# tick-mini-mk-1_1.net
KiCad netlist of a schematic drawn in EAGLE
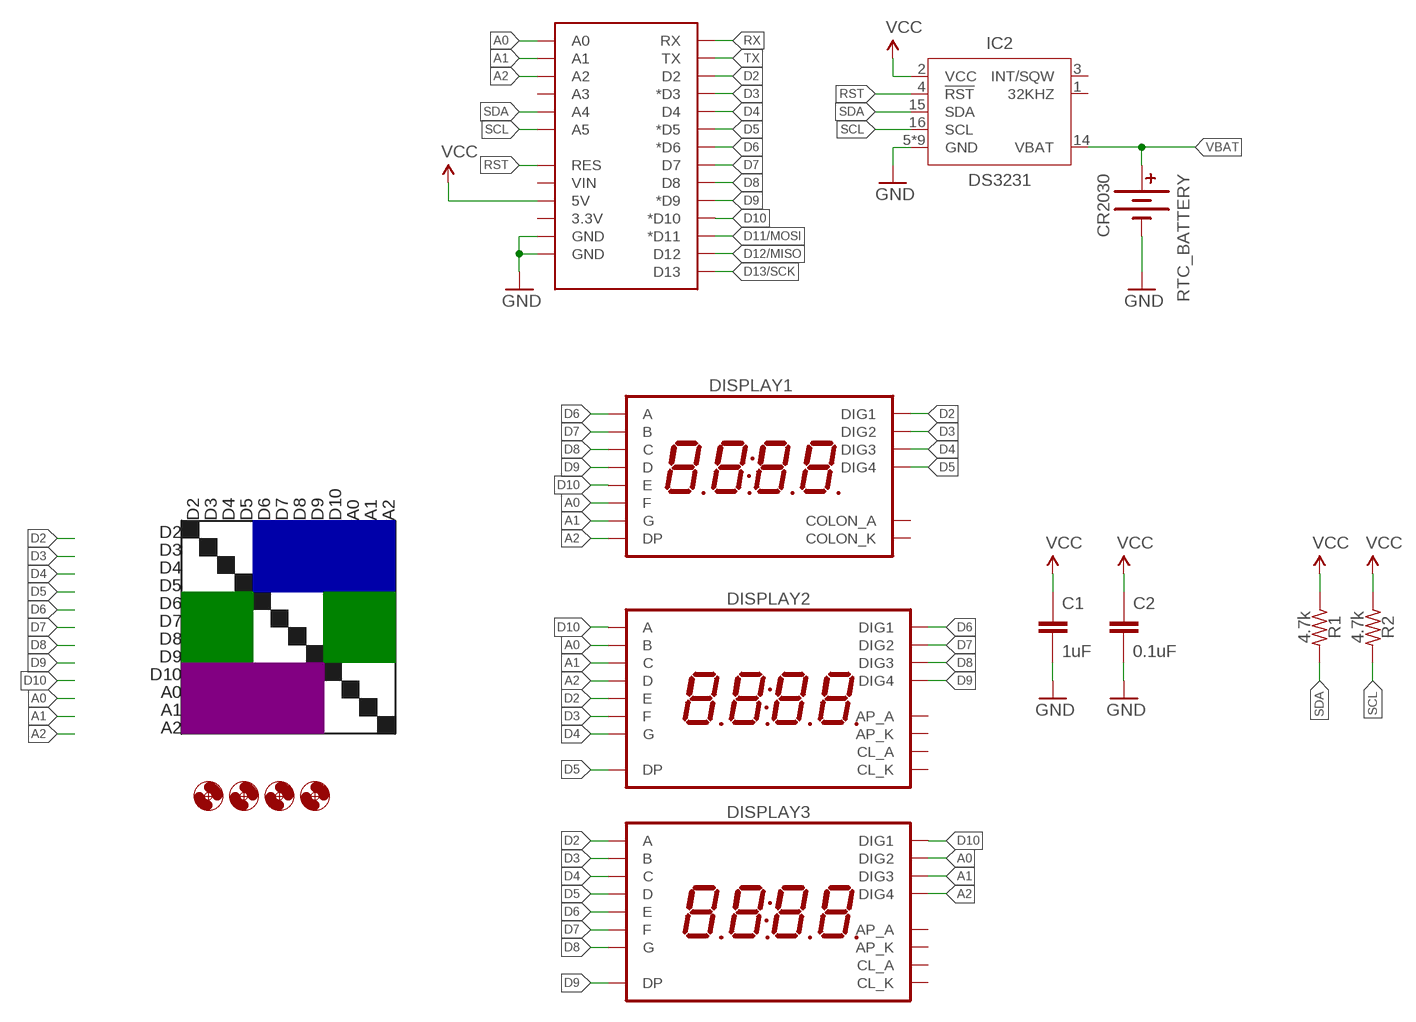
[diagram p0: schematic, sheet 1]

(export (version "E")
  (design (tool "Eeschema 10.0.6"))
  (components
    (comp (ref "C1")
      (value "1uF")
      (footprint "eagle-import:C025-024X044")
      (libsource (lib "eagle-import") (part "CAPACITOR-CERAMIC025-024X044"))
    )
    (comp (ref "C2")
      (value "0.1uF")
      (footprint "eagle-import:C025-024X044")
      (libsource (lib "eagle-import") (part "CAPACITOR-CERAMIC025-024X044"))
    )
    (comp (ref "DISPLAY1")
      (value "7SEG_4DIGIT_COLON14.2MM-CC-NS")
      (footprint "eagle-import:7SEG_4DIG_NS")
      (libsource (lib "eagle-import") (part "7SEG_4DIGIT_COLON14.2MM-CC-NS"))
    )
    (comp (ref "DISPLAY2")
      (value "7SEG_4DIGIT_COLON_APOS")
      (footprint "eagle-import:7SEG_4DIG_10MM")
      (libsource (lib "eagle-import") (part "7SEG_4DIGIT_COLON_APOS"))
    )
    (comp (ref "DISPLAY3")
      (value "7SEG_4DIGIT_COLON_APOS")
      (footprint "eagle-import:7SEG_4DIG_10MM")
      (libsource (lib "eagle-import") (part "7SEG_4DIGIT_COLON_APOS"))
    )
    (comp (ref "H1")
      (value "HOLE#2")
      (footprint "eagle-import:HOLE-#2")
      (libsource (lib "eagle-import") (part "HOLE#2"))
    )
    (comp (ref "H2")
      (value "HOLE#2")
      (footprint "eagle-import:HOLE-#2")
      (libsource (lib "eagle-import") (part "HOLE#2"))
    )
    (comp (ref "H3")
      (value "HOLE#2")
      (footprint "eagle-import:HOLE-#2")
      (libsource (lib "eagle-import") (part "HOLE#2"))
    )
    (comp (ref "H4")
      (value "HOLE#2")
      (footprint "eagle-import:HOLE-#2")
      (libsource (lib "eagle-import") (part "HOLE#2"))
    )
    (comp (ref "IC2")
      (value "DS3231")
      (footprint "eagle-import:SO16W")
      (libsource (lib "eagle-import") (part "DS3231"))
    )
    (comp (ref "R1")
      (value "4.7k")
      (footprint "eagle-import:RESISTOR-AXIAL-PTH-6.35MM")
      (libsource (lib "eagle-import") (part "RESISTORPTH-AXIAL-6.35MM"))
    )
    (comp (ref "R2")
      (value "4.7k")
      (footprint "eagle-import:RESISTOR-AXIAL-PTH-6.35MM")
      (libsource (lib "eagle-import") (part "RESISTORPTH-AXIAL-6.35MM"))
    )
    (comp (ref "RTC_BATTERY")
      (value "CR2030")
      (footprint "eagle-import:BATTCON_20MM_MINE")
      (libsource (lib "eagle-import") (part "BATTERY20MMSMD-MINE"))
    )
    (comp (ref "U$1")
      (value "ARDUINO_SHIELD_SMALLER")
      (footprint "eagle-import:ARDUINO_SHIELD_NOOUTLINE_INSIDE_SMALLER")
      (libsource (lib "eagle-import") (part "ARDUINO_SHIELD_SMALLER"))
    )
  )
  (nets
    (net (code "1") (name "A0") (class "Default")
      (node (ref "DISPLAY1") (pin "P$12") (pinfunction "F_P$12") (pintype "passive"))
      (node (ref "DISPLAY2") (pin "16") (pinfunction "B_16") (pintype "passive"))
      (node (ref "DISPLAY3") (pin "2") (pinfunction "DIG2_2") (pintype "passive"))
      (node (ref "U$1") (pin "A0") (pinfunction "A0_A0") (pintype "bidirectional"))
    )
    (net (code "2") (name "A1") (class "Default")
      (node (ref "DISPLAY1") (pin "P$5") (pinfunction "G_P$5") (pintype "passive"))
      (node (ref "DISPLAY2") (pin "13") (pinfunction "C_13") (pintype "passive"))
      (node (ref "DISPLAY3") (pin "6") (pinfunction "DIG3_6") (pintype "passive"))
      (node (ref "U$1") (pin "A1") (pinfunction "A1_A1") (pintype "bidirectional"))
    )
    (net (code "3") (name "A2") (class "Default")
      (node (ref "DISPLAY1") (pin "P$3") (pinfunction "DP_P$3") (pintype "passive"))
      (node (ref "DISPLAY2") (pin "3") (pinfunction "D_3") (pintype "passive"))
      (node (ref "DISPLAY3") (pin "8") (pinfunction "DIG4_8") (pintype "passive"))
      (node (ref "U$1") (pin "A2") (pinfunction "A2_A2") (pintype "bidirectional"))
    )
    (net (code "4") (name "D2") (class "Default")
      (node (ref "DISPLAY1") (pin "P$14") (pinfunction "DIG1_P$14") (pintype "passive"))
      (node (ref "DISPLAY2") (pin "5") (pinfunction "E_5") (pintype "passive"))
      (node (ref "DISPLAY3") (pin "14") (pinfunction "A_14") (pintype "passive"))
      (node (ref "U$1") (pin "D2") (pinfunction "D2_D2") (pintype "bidirectional"))
    )
    (net (code "5") (name "D3") (class "Default")
      (node (ref "DISPLAY1") (pin "P$11") (pinfunction "DIG2_P$11") (pintype "passive"))
      (node (ref "DISPLAY2") (pin "11") (pinfunction "F_11") (pintype "passive"))
      (node (ref "DISPLAY3") (pin "16") (pinfunction "B_16") (pintype "passive"))
      (node (ref "U$1") (pin "D3") (pinfunction "*D3_D3") (pintype "bidirectional"))
    )
    (net (code "6") (name "D4") (class "Default")
      (node (ref "DISPLAY1") (pin "P$10") (pinfunction "DIG3_P$10") (pintype "passive"))
      (node (ref "DISPLAY2") (pin "15") (pinfunction "G_15") (pintype "passive"))
      (node (ref "DISPLAY3") (pin "13") (pinfunction "C_13") (pintype "passive"))
      (node (ref "U$1") (pin "D4") (pinfunction "D4_D4") (pintype "bidirectional"))
    )
    (net (code "7") (name "D5") (class "Default")
      (node (ref "DISPLAY1") (pin "P$6") (pinfunction "DIG4_P$6") (pintype "passive"))
      (node (ref "DISPLAY2") (pin "7") (pinfunction "DP_7") (pintype "passive"))
      (node (ref "DISPLAY3") (pin "3") (pinfunction "D_3") (pintype "passive"))
      (node (ref "U$1") (pin "D5") (pinfunction "*D5_D5") (pintype "bidirectional"))
    )
    (net (code "8") (name "D6") (class "Default")
      (node (ref "DISPLAY1") (pin "P$13") (pinfunction "A_P$13") (pintype "passive"))
      (node (ref "DISPLAY2") (pin "1") (pinfunction "DIG1_1") (pintype "passive"))
      (node (ref "DISPLAY3") (pin "5") (pinfunction "E_5") (pintype "passive"))
      (node (ref "U$1") (pin "D6") (pinfunction "*D6_D6") (pintype "bidirectional"))
    )
    (net (code "9") (name "D7") (class "Default")
      (node (ref "DISPLAY1") (pin "P$9") (pinfunction "B_P$9") (pintype "passive"))
      (node (ref "DISPLAY2") (pin "2") (pinfunction "DIG2_2") (pintype "passive"))
      (node (ref "DISPLAY3") (pin "11") (pinfunction "F_11") (pintype "passive"))
      (node (ref "U$1") (pin "D7") (pinfunction "D7_D7") (pintype "bidirectional"))
    )
    (net (code "10") (name "D8") (class "Default")
      (node (ref "DISPLAY1") (pin "P$4") (pinfunction "C_P$4") (pintype "passive"))
      (node (ref "DISPLAY2") (pin "6") (pinfunction "DIG3_6") (pintype "passive"))
      (node (ref "DISPLAY3") (pin "15") (pinfunction "G_15") (pintype "passive"))
      (node (ref "U$1") (pin "D8") (pinfunction "D8_D8") (pintype "bidirectional"))
    )
    (net (code "11") (name "D9") (class "Default")
      (node (ref "DISPLAY1") (pin "P$2") (pinfunction "D_P$2") (pintype "passive"))
      (node (ref "DISPLAY2") (pin "8") (pinfunction "DIG4_8") (pintype "passive"))
      (node (ref "DISPLAY3") (pin "7") (pinfunction "DP_7") (pintype "passive"))
      (node (ref "U$1") (pin "D9") (pinfunction "*D9_D9") (pintype "bidirectional"))
    )
    (net (code "12") (name "D10") (class "Default")
      (node (ref "DISPLAY1") (pin "P$1") (pinfunction "E_P$1") (pintype "passive"))
      (node (ref "DISPLAY2") (pin "14") (pinfunction "A_14") (pintype "passive"))
      (node (ref "DISPLAY3") (pin "1") (pinfunction "DIG1_1") (pintype "passive"))
      (node (ref "U$1") (pin "D10") (pinfunction "*D10_D10") (pintype "bidirectional"))
    )
    (net (code "13") (name "D11{slash}MOSI") (class "Default")
      (node (ref "U$1") (pin "D11") (pinfunction "*D11_D11") (pintype "bidirectional"))
    )
    (net (code "14") (name "D12{slash}MISO") (class "Default")
      (node (ref "U$1") (pin "D12") (pinfunction "D12_D12") (pintype "bidirectional"))
    )
    (net (code "15") (name "D13{slash}SCK") (class "Default")
      (node (ref "U$1") (pin "D13") (pinfunction "D13_D13") (pintype "bidirectional"))
    )
    (net (code "16") (name "GND") (class "Default")
      (node (ref "C1") (pin "2") (pinfunction "2_2") (pintype "passive"))
      (node (ref "C2") (pin "2") (pinfunction "2_2") (pintype "passive"))
      (node (ref "IC2") (pin "10") (pinfunction "GND_10") (pintype "bidirectional"))
      (node (ref "IC2") (pin "11") (pinfunction "GND_11") (pintype "bidirectional"))
      (node (ref "IC2") (pin "12") (pinfunction "GND_12") (pintype "bidirectional"))
      (node (ref "IC2") (pin "13") (pinfunction "GND_13") (pintype "bidirectional"))
      (node (ref "IC2") (pin "5") (pinfunction "GND_5") (pintype "bidirectional"))
      (node (ref "IC2") (pin "6") (pinfunction "GND_6") (pintype "bidirectional"))
      (node (ref "IC2") (pin "7") (pinfunction "GND_7") (pintype "bidirectional"))
      (node (ref "IC2") (pin "8") (pinfunction "GND_8") (pintype "bidirectional"))
      (node (ref "IC2") (pin "9") (pinfunction "GND_9") (pintype "bidirectional"))
      (node (ref "RTC_BATTERY") (pin "BOTTOM") (pinfunction "-_BOTTOM") (pintype "power_in"))
      (node (ref "U$1") (pin "GND@0") (pinfunction "GND_GND@0") (pintype "bidirectional"))
      (node (ref "U$1") (pin "GND@1") (pinfunction "GND_GND@1") (pintype "bidirectional"))
    )
    (net (code "17") (name "RST") (class "Default")
      (node (ref "IC2") (pin "4") (pinfunction "~{RST}_4") (pintype "bidirectional"))
      (node (ref "U$1") (pin "RES") (pinfunction "RES_RES") (pintype "bidirectional"))
    )
    (net (code "18") (name "RX") (class "Default")
      (node (ref "U$1") (pin "RX") (pinfunction "RX_RX") (pintype "bidirectional"))
    )
    (net (code "19") (name "SCL") (class "Default")
      (node (ref "IC2") (pin "16") (pinfunction "SCL_16") (pintype "bidirectional"))
      (node (ref "R2") (pin "P$2") (pinfunction "2_P$2") (pintype "passive"))
      (node (ref "U$1") (pin "A5") (pinfunction "A5_A5") (pintype "bidirectional"))
    )
    (net (code "20") (name "SDA") (class "Default")
      (node (ref "IC2") (pin "15") (pinfunction "SDA_15") (pintype "bidirectional"))
      (node (ref "R1") (pin "P$2") (pinfunction "2_P$2") (pintype "passive"))
      (node (ref "U$1") (pin "A4") (pinfunction "A4_A4") (pintype "bidirectional"))
    )
    (net (code "21") (name "TX") (class "Default")
      (node (ref "U$1") (pin "TX") (pinfunction "TX_TX") (pintype "bidirectional"))
    )
    (net (code "22") (name "VBAT") (class "Default")
      (node (ref "IC2") (pin "14") (pinfunction "VBAT_14") (pintype "bidirectional"))
      (node (ref "RTC_BATTERY") (pin "TOP@1") (pinfunction "+_TOP@1") (pintype "power_in"))
      (node (ref "RTC_BATTERY") (pin "TOP@2") (pinfunction "+_TOP@2") (pintype "power_in"))
    )
    (net (code "23") (name "VCC") (class "Default")
      (node (ref "C1") (pin "1") (pinfunction "1_1") (pintype "passive"))
      (node (ref "C2") (pin "1") (pinfunction "1_1") (pintype "passive"))
      (node (ref "IC2") (pin "2") (pinfunction "VCC_2") (pintype "bidirectional"))
      (node (ref "R1") (pin "P$1") (pinfunction "1_P$1") (pintype "passive"))
      (node (ref "R2") (pin "P$1") (pinfunction "1_P$1") (pintype "passive"))
      (node (ref "U$1") (pin "5V") (pinfunction "5V_5V") (pintype "bidirectional"))
    )
    (net (code "24") (name "unconnected-(DISPLAY1-COLON_A-PadP$8)") (class "Default")
      (node (ref "DISPLAY1") (pin "P$8") (pinfunction "COLON_A_P$8") (pintype "passive"))
    )
    (net (code "25") (name "unconnected-(DISPLAY1-COLON_K-PadP$7)") (class "Default")
      (node (ref "DISPLAY1") (pin "P$7") (pinfunction "COLON_K_P$7") (pintype "passive"))
    )
    (net (code "26") (name "unconnected-(DISPLAY2-AP_A-Pad10)") (class "Default")
      (node (ref "DISPLAY2") (pin "10") (pinfunction "AP_A_10") (pintype "bidirectional"))
    )
    (net (code "27") (name "unconnected-(DISPLAY2-AP_K-Pad9)") (class "Default")
      (node (ref "DISPLAY2") (pin "9") (pinfunction "AP_K_9") (pintype "bidirectional"))
    )
    (net (code "28") (name "unconnected-(DISPLAY2-CL_A-Pad4)") (class "Default")
      (node (ref "DISPLAY2") (pin "4") (pinfunction "CL_A_4") (pintype "passive"))
    )
    (net (code "29") (name "unconnected-(DISPLAY2-CL_K-Pad12)") (class "Default")
      (node (ref "DISPLAY2") (pin "12") (pinfunction "CL_K_12") (pintype "passive"))
    )
    (net (code "30") (name "unconnected-(DISPLAY3-AP_A-Pad10)") (class "Default")
      (node (ref "DISPLAY3") (pin "10") (pinfunction "AP_A_10") (pintype "bidirectional"))
    )
    (net (code "31") (name "unconnected-(DISPLAY3-AP_K-Pad9)") (class "Default")
      (node (ref "DISPLAY3") (pin "9") (pinfunction "AP_K_9") (pintype "bidirectional"))
    )
    (net (code "32") (name "unconnected-(DISPLAY3-CL_A-Pad4)") (class "Default")
      (node (ref "DISPLAY3") (pin "4") (pinfunction "CL_A_4") (pintype "passive"))
    )
    (net (code "33") (name "unconnected-(DISPLAY3-CL_K-Pad12)") (class "Default")
      (node (ref "DISPLAY3") (pin "12") (pinfunction "CL_K_12") (pintype "passive"))
    )
    (net (code "34") (name "unconnected-(IC2-32KHZ-Pad1)") (class "Default")
      (node (ref "IC2") (pin "1") (pinfunction "32KHZ_1") (pintype "bidirectional"))
    )
    (net (code "35") (name "unconnected-(IC2-INT{slash}SQW-Pad3)") (class "Default")
      (node (ref "IC2") (pin "3") (pinfunction "INT/SQW_3") (pintype "bidirectional"))
    )
    (net (code "36") (name "unconnected-(U$1-Pad3.3V)") (class "Default")
      (node (ref "U$1") (pin "3.3V") (pinfunction "3.3V_3.3V") (pintype "bidirectional"))
    )
    (net (code "37") (name "unconnected-(U$1-PadA3)") (class "Default")
      (node (ref "U$1") (pin "A3") (pinfunction "A3_A3") (pintype "bidirectional"))
    )
    (net (code "38") (name "unconnected-(U$1-PadVIN)") (class "Default")
      (node (ref "U$1") (pin "VIN") (pinfunction "VIN_VIN") (pintype "bidirectional"))
    )
  )
)
